# controle_detc.net
KiCad netlist of a schematic drawn in EAGLE
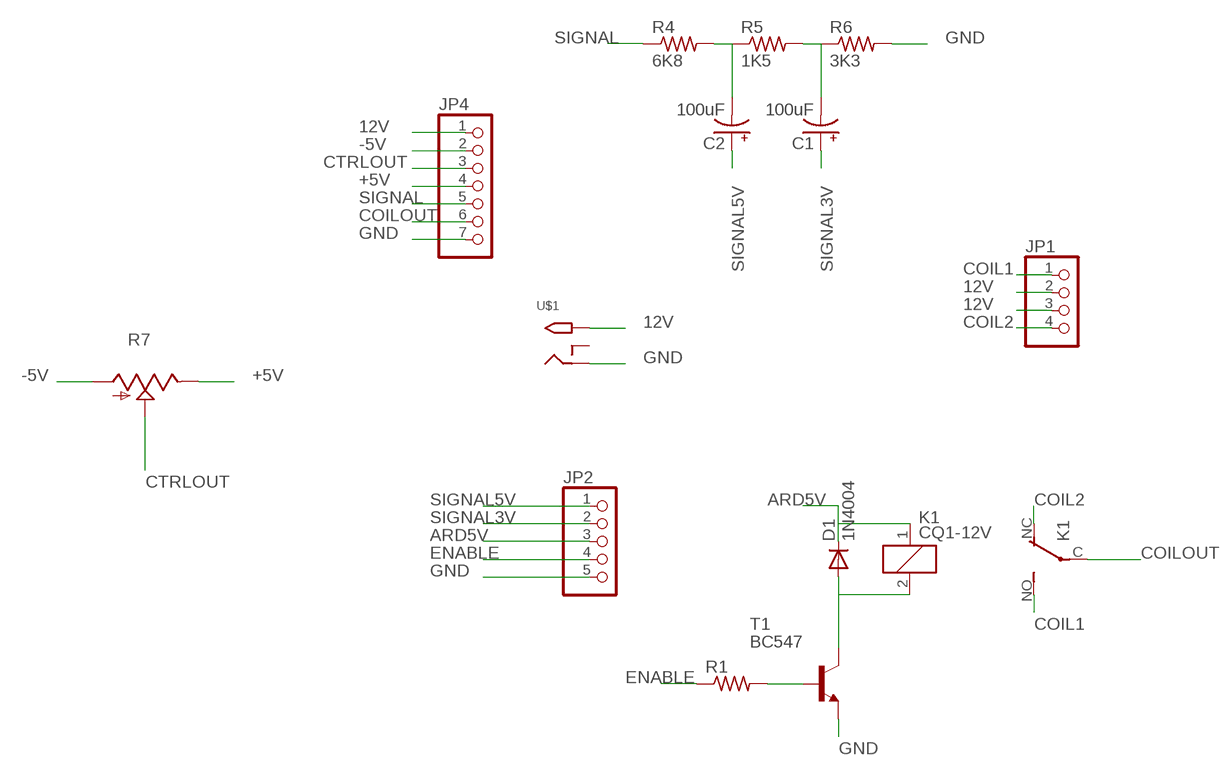
[diagram p0: schematic, sheet 1]

(export (version "E")
  (design (tool "Eeschema 10.0.6"))
  (components
    (comp (ref "C1")
      (value "100uF")
      (footprint "eagle-import:E5-8,5")
      (libsource (lib "eagle-import") (part "CPOL-USE5-8.5"))
    )
    (comp (ref "C2")
      (value "100uF")
      (footprint "eagle-import:E5-8,5")
      (libsource (lib "eagle-import") (part "CPOL-USE5-8.5"))
    )
    (comp (ref "D1")
      (value "1N4004")
      (footprint "eagle-import:DO41-10")
      (libsource (lib "eagle-import") (part "1N4004"))
    )
    (comp (ref "JP1")
      (value "PINHD-1X4")
      (footprint "eagle-import:1X04")
      (libsource (lib "eagle-import") (part "PINHD-1X4"))
    )
    (comp (ref "JP2")
      (value "PINHD-1X5")
      (footprint "eagle-import:1X05")
      (libsource (lib "eagle-import") (part "PINHD-1X5"))
    )
    (comp (ref "JP4")
      (value "PINHD-1X7")
      (footprint "eagle-import:1X07")
      (libsource (lib "eagle-import") (part "PINHD-1X7"))
    )
    (comp (ref "K1")
      (value "CQ1-12V")
      (footprint "eagle-import:CQ1")
      (libsource (lib "eagle-import") (part "CQ1-12V"))
    )
    (comp (ref "R1")
      (value "R-US_0207/7")
      (footprint "eagle-import:0207_7")
      (libsource (lib "eagle-import") (part "R-US_0207/7"))
    )
    (comp (ref "R4")
      (value "6K8")
      (footprint "eagle-import:0207_7")
      (libsource (lib "eagle-import") (part "R-US_0207/7"))
    )
    (comp (ref "R5")
      (value "1K5")
      (footprint "eagle-import:0207_7")
      (libsource (lib "eagle-import") (part "R-US_0207/7"))
    )
    (comp (ref "R6")
      (value "3K3")
      (footprint "eagle-import:0207_7")
      (libsource (lib "eagle-import") (part "R-US_0207/7"))
    )
    (comp (ref "R7")
      (value "TRIM_US-S64W")
      (footprint "eagle-import:S64W")
      (libsource (lib "eagle-import") (part "TRIM_US-S64W"))
    )
    (comp (ref "T1")
      (value "BC547")
      (footprint "eagle-import:TO92")
      (libsource (lib "eagle-import") (part "BC547"))
    )
    (comp (ref "U$1")
      (value "2.1MMJACKTHM")
      (footprint "eagle-import:PJ-102A")
      (libsource (lib "eagle-import") (part "2.1MMJACKTHM"))
    )
  )
  (nets
    (net (code "1") (name "/+5V") (class "Default")
      (node (ref "JP4") (pin "4") (pinfunction "4_4") (pintype "passive"))
      (node (ref "R7") (pin "E") (pinfunction "E_E") (pintype "passive"))
    )
    (net (code "2") (name "/-5V") (class "Default")
      (node (ref "JP4") (pin "2") (pinfunction "2_2") (pintype "passive"))
      (node (ref "R7") (pin "A") (pinfunction "A_A") (pintype "passive"))
    )
    (net (code "3") (name "/12V") (class "Default")
      (node (ref "JP1") (pin "2") (pinfunction "2_2") (pintype "passive"))
      (node (ref "JP1") (pin "3") (pinfunction "3_3") (pintype "passive"))
      (node (ref "JP4") (pin "1") (pinfunction "1_1") (pintype "passive"))
      (node (ref "U$1") (pin "TIP") (pinfunction "TIP_TIP") (pintype "bidirectional"))
    )
    (net (code "4") (name "/ARD5V") (class "Default")
      (node (ref "D1") (pin "C") (pinfunction "C_C") (pintype "passive"))
      (node (ref "JP2") (pin "3") (pinfunction "3_3") (pintype "passive"))
      (node (ref "K1") (pin "1") (pinfunction "1_1") (pintype "passive"))
    )
    (net (code "5") (name "/COIL1") (class "Default")
      (node (ref "JP1") (pin "1") (pinfunction "1_1") (pintype "passive"))
      (node (ref "K1") (pin "NO") (pinfunction "S_NO") (pintype "passive"))
    )
    (net (code "6") (name "/COIL2") (class "Default")
      (node (ref "JP1") (pin "4") (pinfunction "4_4") (pintype "passive"))
      (node (ref "K1") (pin "NC") (pinfunction "O_NC") (pintype "passive"))
    )
    (net (code "7") (name "/COILOUT") (class "Default")
      (node (ref "JP4") (pin "6") (pinfunction "6_6") (pintype "passive"))
      (node (ref "K1") (pin "C") (pinfunction "P_C") (pintype "passive"))
    )
    (net (code "8") (name "/CTRLOUT") (class "Default")
      (node (ref "JP4") (pin "3") (pinfunction "3_3") (pintype "passive"))
      (node (ref "R7") (pin "S") (pinfunction "S_S") (pintype "passive"))
    )
    (net (code "9") (name "/ENABLE") (class "Default")
      (node (ref "JP2") (pin "4") (pinfunction "4_4") (pintype "passive"))
      (node (ref "R1") (pin "1") (pinfunction "1_1") (pintype "passive"))
    )
    (net (code "10") (name "/GND") (class "Default")
      (node (ref "JP2") (pin "5") (pinfunction "5_5") (pintype "passive"))
      (node (ref "JP4") (pin "7") (pinfunction "7_7") (pintype "passive"))
      (node (ref "R6") (pin "2") (pinfunction "2_2") (pintype "passive"))
      (node (ref "T1") (pin "1") (pinfunction "E_1") (pintype "passive"))
      (node (ref "U$1") (pin "RING") (pinfunction "RING_RING") (pintype "bidirectional"))
    )
    (net (code "11") (name "/SIGNAL") (class "Default")
      (node (ref "JP4") (pin "5") (pinfunction "5_5") (pintype "passive"))
      (node (ref "R4") (pin "1") (pinfunction "1_1") (pintype "passive"))
    )
    (net (code "12") (name "/SIGNAL3V") (class "Default")
      (node (ref "C1") (pin "+") (pinfunction "+_+") (pintype "passive"))
      (node (ref "JP2") (pin "2") (pinfunction "2_2") (pintype "passive"))
    )
    (net (code "13") (name "/SIGNAL5V") (class "Default")
      (node (ref "C2") (pin "+") (pinfunction "+_+") (pintype "passive"))
      (node (ref "JP2") (pin "1") (pinfunction "1_1") (pintype "passive"))
    )
    (net (code "14") (name "Net-(C1-Pad-)") (class "Default")
      (node (ref "C1") (pin "-") (pinfunction "-_-") (pintype "passive"))
      (node (ref "R5") (pin "2") (pinfunction "2_2") (pintype "passive"))
      (node (ref "R6") (pin "1") (pinfunction "1_1") (pintype "passive"))
    )
    (net (code "15") (name "Net-(C2-Pad-)") (class "Default")
      (node (ref "C2") (pin "-") (pinfunction "-_-") (pintype "passive"))
      (node (ref "R4") (pin "2") (pinfunction "2_2") (pintype "passive"))
      (node (ref "R5") (pin "1") (pinfunction "1_1") (pintype "passive"))
    )
    (net (code "16") (name "Net-(T1-B)") (class "Default")
      (node (ref "R1") (pin "2") (pinfunction "2_2") (pintype "passive"))
      (node (ref "T1") (pin "2") (pinfunction "B_2") (pintype "passive"))
    )
    (net (code "17") (name "Net-(T1-C)") (class "Default")
      (node (ref "D1") (pin "A") (pinfunction "A_A") (pintype "passive"))
      (node (ref "K1") (pin "2") (pinfunction "2_2") (pintype "passive"))
      (node (ref "T1") (pin "3") (pinfunction "C_3") (pintype "passive"))
    )
    (net (code "18") (name "unconnected-(U$1-PadRING_SW)") (class "Default")
      (node (ref "U$1") (pin "RING_SW") (pinfunction "RING_SW_RING_SW") (pintype "bidirectional"))
    )
  )
)
